# Blank.net
KiCad netlist of a schematic drawn in Altium Designer
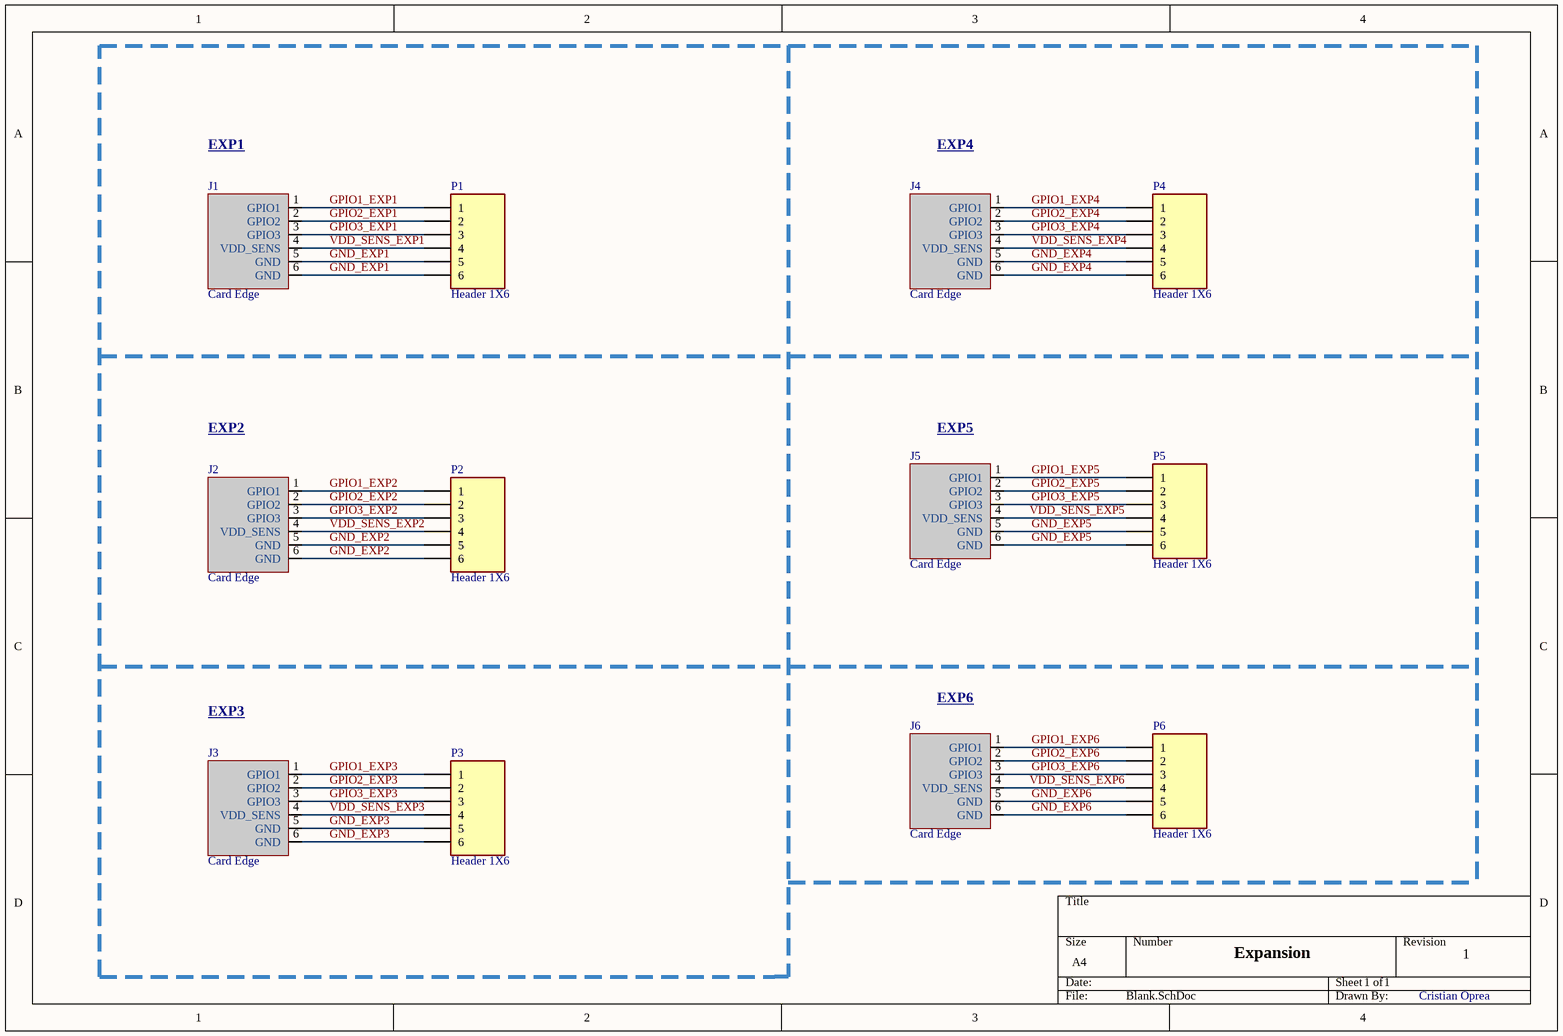
[diagram p0: Blank.SchDoc]

(export (version "E")
  (design (tool "Eeschema 10.0.6"))
  (components
    (comp (ref "J1")
      (value "Card Edge")
      (footprint "Card Edge")
      (description "Card Edge pads for 2.54 mm pitch edge connector")
      (libsource (lib "Schlib1") (part "Card Edge"))
    )
    (comp (ref "J2")
      (value "Card Edge")
      (footprint "Card Edge")
      (description "Card Edge pads for 2.54 mm pitch edge connector")
      (libsource (lib "Schlib1") (part "Card Edge"))
    )
    (comp (ref "J3")
      (value "Card Edge")
      (footprint "Card Edge")
      (description "Card Edge pads for 2.54 mm pitch edge connector")
      (libsource (lib "Schlib1") (part "Card Edge"))
    )
    (comp (ref "J4")
      (value "Card Edge")
      (footprint "Card Edge")
      (description "Card Edge pads for 2.54 mm pitch edge connector")
      (libsource (lib "Schlib1") (part "Card Edge"))
    )
    (comp (ref "J5")
      (value "Card Edge")
      (footprint "Card Edge")
      (description "Card Edge pads for 2.54 mm pitch edge connector")
      (libsource (lib "Schlib1") (part "Card Edge"))
    )
    (comp (ref "J6")
      (value "Card Edge")
      (footprint "Card Edge")
      (description "Card Edge pads for 2.54 mm pitch edge connector")
      (libsource (lib "Schlib1") (part "Card Edge"))
    )
    (comp (ref "P1")
      (value "Header 1X6")
      (footprint "HEADER_1x6_2.54")
      (description "Header,6-Pin, Single row")
      (fields (field (name "PUBLISHER") "Altium Limited"))
      (libsource (lib "Schlib1") (part "Header 1X6"))
    )
    (comp (ref "P2")
      (value "Header 1X6")
      (footprint "HEADER_1x6_2.54")
      (description "Header,6-Pin, Single row")
      (fields (field (name "PUBLISHER") "Altium Limited"))
      (libsource (lib "Schlib1") (part "Header 1X6"))
    )
    (comp (ref "P3")
      (value "Header 1X6")
      (footprint "HEADER_1x6_2.54")
      (description "Header,6-Pin, Single row")
      (fields (field (name "PUBLISHER") "Altium Limited"))
      (libsource (lib "Schlib1") (part "Header 1X6"))
    )
    (comp (ref "P4")
      (value "Header 1X6")
      (footprint "HEADER_1x6_2.54")
      (description "Header,6-Pin, Single row")
      (fields (field (name "PUBLISHER") "Altium Limited"))
      (libsource (lib "Schlib1") (part "Header 1X6"))
    )
    (comp (ref "P5")
      (value "Header 1X6")
      (footprint "HEADER_1x6_2.54")
      (description "Header,6-Pin, Single row")
      (fields (field (name "PUBLISHER") "Altium Limited"))
      (libsource (lib "Schlib1") (part "Header 1X6"))
    )
    (comp (ref "P6")
      (value "Header 1X6")
      (footprint "HEADER_1x6_2.54")
      (description "Header,6-Pin, Single row")
      (fields (field (name "PUBLISHER") "Altium Limited"))
      (libsource (lib "Schlib1") (part "Header 1X6"))
    )
  )
  (nets
    (net (code "1") (name "/GND_EXP1") (class "Default")
      (node (ref "J1") (pin "5") (pinfunction "GND_5") (pintype "passive"))
      (node (ref "J1") (pin "6") (pinfunction "GND_6") (pintype "passive"))
      (node (ref "P1") (pin "5") (pinfunction "5_5") (pintype "passive"))
      (node (ref "P1") (pin "6") (pinfunction "6_6") (pintype "passive"))
    )
    (net (code "2") (name "/GND_EXP2") (class "Default")
      (node (ref "J2") (pin "5") (pinfunction "GND_5") (pintype "passive"))
      (node (ref "J2") (pin "6") (pinfunction "GND_6") (pintype "passive"))
      (node (ref "P2") (pin "5") (pinfunction "5_5") (pintype "passive"))
      (node (ref "P2") (pin "6") (pinfunction "6_6") (pintype "passive"))
    )
    (net (code "3") (name "/GND_EXP3") (class "Default")
      (node (ref "J3") (pin "5") (pinfunction "GND_5") (pintype "passive"))
      (node (ref "J3") (pin "6") (pinfunction "GND_6") (pintype "passive"))
      (node (ref "P3") (pin "5") (pinfunction "5_5") (pintype "passive"))
      (node (ref "P3") (pin "6") (pinfunction "6_6") (pintype "passive"))
    )
    (net (code "4") (name "/GND_EXP4") (class "Default")
      (node (ref "J4") (pin "5") (pinfunction "GND_5") (pintype "passive"))
      (node (ref "J4") (pin "6") (pinfunction "GND_6") (pintype "passive"))
      (node (ref "P4") (pin "5") (pinfunction "5_5") (pintype "passive"))
      (node (ref "P4") (pin "6") (pinfunction "6_6") (pintype "passive"))
    )
    (net (code "5") (name "/GND_EXP5") (class "Default")
      (node (ref "J5") (pin "5") (pinfunction "GND_5") (pintype "passive"))
      (node (ref "J5") (pin "6") (pinfunction "GND_6") (pintype "passive"))
      (node (ref "P5") (pin "5") (pinfunction "5_5") (pintype "passive"))
      (node (ref "P5") (pin "6") (pinfunction "6_6") (pintype "passive"))
    )
    (net (code "6") (name "/GND_EXP6") (class "Default")
      (node (ref "J6") (pin "5") (pinfunction "GND_5") (pintype "passive"))
      (node (ref "J6") (pin "6") (pinfunction "GND_6") (pintype "passive"))
      (node (ref "P6") (pin "5") (pinfunction "5_5") (pintype "passive"))
      (node (ref "P6") (pin "6") (pinfunction "6_6") (pintype "passive"))
    )
    (net (code "7") (name "/GPIO1_EXP1") (class "Default")
      (node (ref "J1") (pin "1") (pinfunction "GPIO1_1") (pintype "passive"))
      (node (ref "P1") (pin "1") (pinfunction "1_1") (pintype "passive"))
    )
    (net (code "8") (name "/GPIO1_EXP2") (class "Default")
      (node (ref "J2") (pin "1") (pinfunction "GPIO1_1") (pintype "passive"))
      (node (ref "P2") (pin "1") (pinfunction "1_1") (pintype "passive"))
    )
    (net (code "9") (name "/GPIO1_EXP3") (class "Default")
      (node (ref "J3") (pin "1") (pinfunction "GPIO1_1") (pintype "passive"))
      (node (ref "P3") (pin "1") (pinfunction "1_1") (pintype "passive"))
    )
    (net (code "10") (name "/GPIO1_EXP4") (class "Default")
      (node (ref "J4") (pin "1") (pinfunction "GPIO1_1") (pintype "passive"))
      (node (ref "P4") (pin "1") (pinfunction "1_1") (pintype "passive"))
    )
    (net (code "11") (name "/GPIO1_EXP5") (class "Default")
      (node (ref "J5") (pin "1") (pinfunction "GPIO1_1") (pintype "passive"))
      (node (ref "P5") (pin "1") (pinfunction "1_1") (pintype "passive"))
    )
    (net (code "12") (name "/GPIO1_EXP6") (class "Default")
      (node (ref "J6") (pin "1") (pinfunction "GPIO1_1") (pintype "passive"))
      (node (ref "P6") (pin "1") (pinfunction "1_1") (pintype "passive"))
    )
    (net (code "13") (name "/GPIO2_EXP1") (class "Default")
      (node (ref "J1") (pin "2") (pinfunction "GPIO2_2") (pintype "passive"))
      (node (ref "P1") (pin "2") (pinfunction "2_2") (pintype "passive"))
    )
    (net (code "14") (name "/GPIO2_EXP2") (class "Default")
      (node (ref "J2") (pin "2") (pinfunction "GPIO2_2") (pintype "passive"))
      (node (ref "P2") (pin "2") (pinfunction "2_2") (pintype "passive"))
    )
    (net (code "15") (name "/GPIO2_EXP3") (class "Default")
      (node (ref "J3") (pin "2") (pinfunction "GPIO2_2") (pintype "passive"))
      (node (ref "P3") (pin "2") (pinfunction "2_2") (pintype "passive"))
    )
    (net (code "16") (name "/GPIO2_EXP4") (class "Default")
      (node (ref "J4") (pin "2") (pinfunction "GPIO2_2") (pintype "passive"))
      (node (ref "P4") (pin "2") (pinfunction "2_2") (pintype "passive"))
    )
    (net (code "17") (name "/GPIO2_EXP5") (class "Default")
      (node (ref "J5") (pin "2") (pinfunction "GPIO2_2") (pintype "passive"))
      (node (ref "P5") (pin "2") (pinfunction "2_2") (pintype "passive"))
    )
    (net (code "18") (name "/GPIO2_EXP6") (class "Default")
      (node (ref "J6") (pin "2") (pinfunction "GPIO2_2") (pintype "passive"))
      (node (ref "P6") (pin "2") (pinfunction "2_2") (pintype "passive"))
    )
    (net (code "19") (name "/GPIO3_EXP1") (class "Default")
      (node (ref "J1") (pin "3") (pinfunction "GPIO3_3") (pintype "passive"))
      (node (ref "P1") (pin "3") (pinfunction "3_3") (pintype "passive"))
    )
    (net (code "20") (name "/GPIO3_EXP2") (class "Default")
      (node (ref "J2") (pin "3") (pinfunction "GPIO3_3") (pintype "passive"))
      (node (ref "P2") (pin "3") (pinfunction "3_3") (pintype "passive"))
    )
    (net (code "21") (name "/GPIO3_EXP3") (class "Default")
      (node (ref "J3") (pin "3") (pinfunction "GPIO3_3") (pintype "passive"))
      (node (ref "P3") (pin "3") (pinfunction "3_3") (pintype "passive"))
    )
    (net (code "22") (name "/GPIO3_EXP4") (class "Default")
      (node (ref "J4") (pin "3") (pinfunction "GPIO3_3") (pintype "passive"))
      (node (ref "P4") (pin "3") (pinfunction "3_3") (pintype "passive"))
    )
    (net (code "23") (name "/GPIO3_EXP5") (class "Default")
      (node (ref "J5") (pin "3") (pinfunction "GPIO3_3") (pintype "passive"))
      (node (ref "P5") (pin "3") (pinfunction "3_3") (pintype "passive"))
    )
    (net (code "24") (name "/GPIO3_EXP6") (class "Default")
      (node (ref "J6") (pin "3") (pinfunction "GPIO3_3") (pintype "passive"))
      (node (ref "P6") (pin "3") (pinfunction "3_3") (pintype "passive"))
    )
    (net (code "25") (name "/VDD_SENS_EXP1") (class "Default")
      (node (ref "J1") (pin "4") (pinfunction "VDD_SENS_4") (pintype "passive"))
      (node (ref "P1") (pin "4") (pinfunction "4_4") (pintype "passive"))
    )
    (net (code "26") (name "/VDD_SENS_EXP2") (class "Default")
      (node (ref "J2") (pin "4") (pinfunction "VDD_SENS_4") (pintype "passive"))
      (node (ref "P2") (pin "4") (pinfunction "4_4") (pintype "passive"))
    )
    (net (code "27") (name "/VDD_SENS_EXP3") (class "Default")
      (node (ref "J3") (pin "4") (pinfunction "VDD_SENS_4") (pintype "passive"))
      (node (ref "P3") (pin "4") (pinfunction "4_4") (pintype "passive"))
    )
    (net (code "28") (name "/VDD_SENS_EXP4") (class "Default")
      (node (ref "J4") (pin "4") (pinfunction "VDD_SENS_4") (pintype "passive"))
      (node (ref "P4") (pin "4") (pinfunction "4_4") (pintype "passive"))
    )
    (net (code "29") (name "/VDD_SENS_EXP5") (class "Default")
      (node (ref "J5") (pin "4") (pinfunction "VDD_SENS_4") (pintype "passive"))
      (node (ref "P5") (pin "4") (pinfunction "4_4") (pintype "passive"))
    )
    (net (code "30") (name "/VDD_SENS_EXP6") (class "Default")
      (node (ref "J6") (pin "4") (pinfunction "VDD_SENS_4") (pintype "passive"))
      (node (ref "P6") (pin "4") (pinfunction "4_4") (pintype "passive"))
    )
  )
)
